# LINEARDriver_MCU.net
KiCad netlist of a schematic drawn in Altium Designer
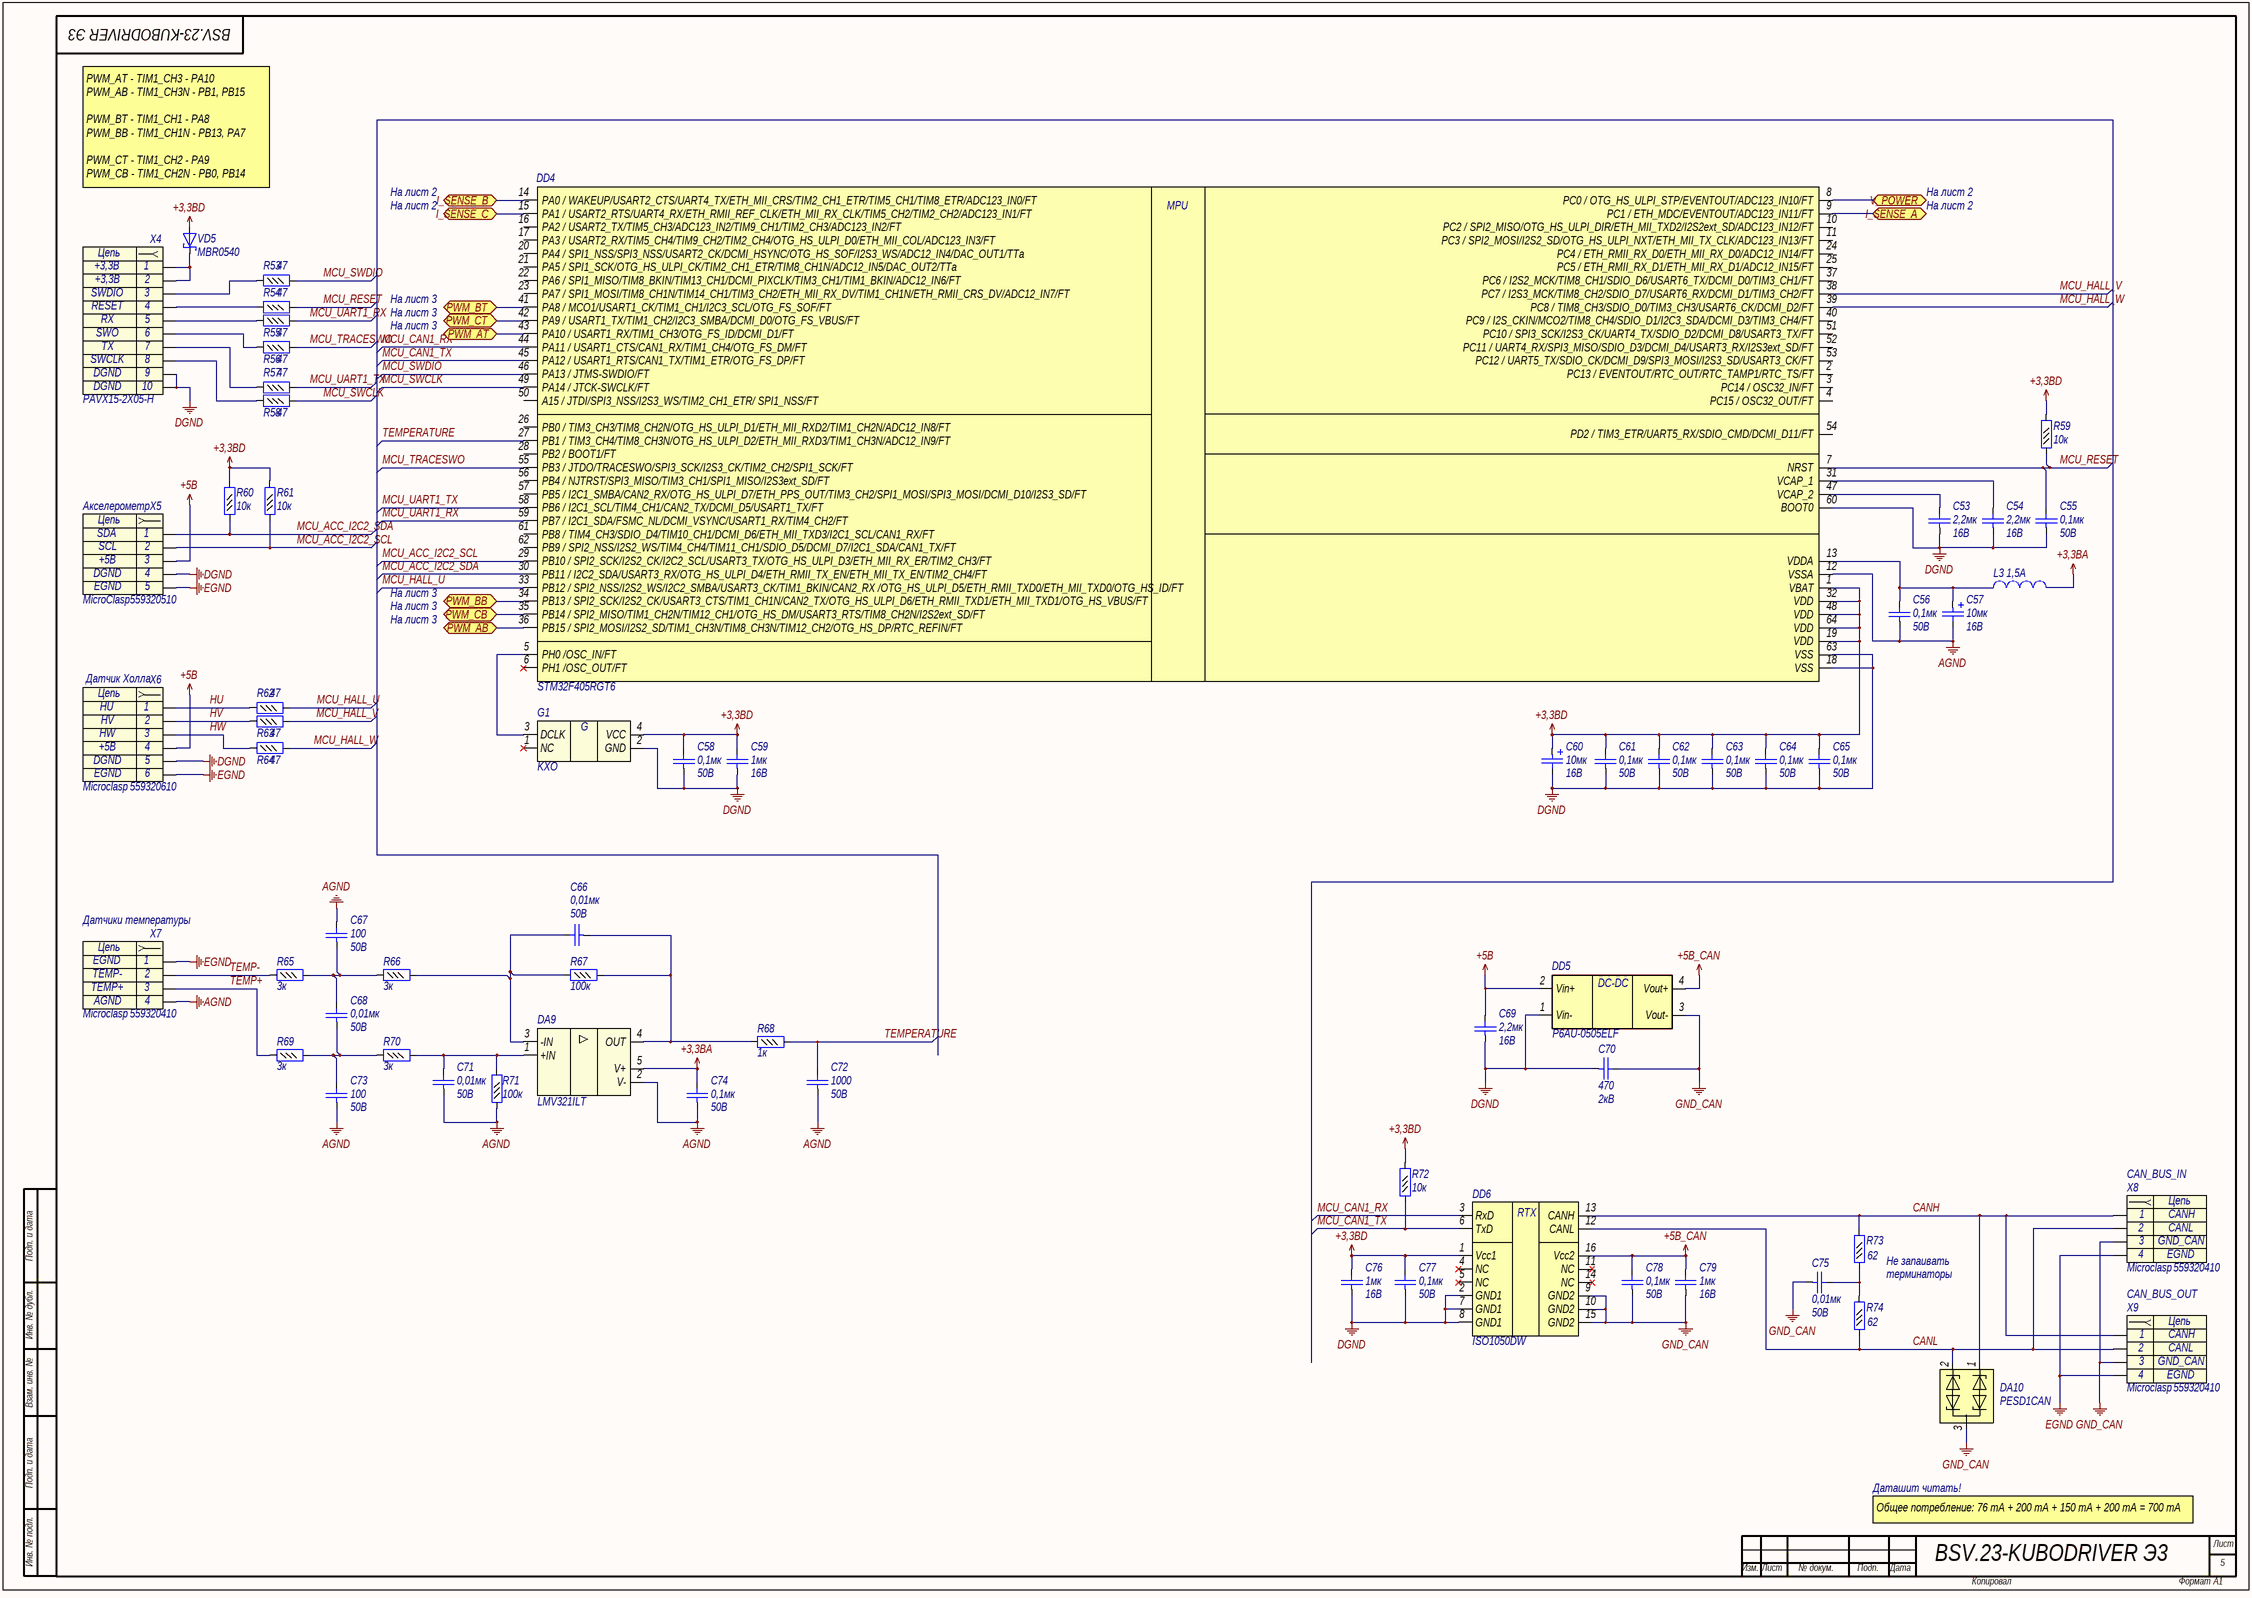
[diagram p0: LINEARDriver_MCU.SchDoc]

(export (version "E")
  (design (tool "Eeschema 10.0.6"))
  (components
    (comp (ref "C53")
      (value "2,2мк")
      (footprint "C0603")
      (description "Конденсатор")
      (fields (field (name "VOLTAGE") "16B") (field (name "PART NUMBER") "GRM188Z71C225ME43J"))
      (libsource (lib "MOP44") (part "Capacitor"))
    )
    (comp (ref "C54")
      (value "2,2мк")
      (footprint "C0603")
      (description "Конденсатор")
      (fields (field (name "VOLTAGE") "16B") (field (name "PART NUMBER") "GRM188Z71C225ME43J"))
      (libsource (lib "MOP44") (part "Capacitor"))
    )
    (comp (ref "C55")
      (value "0,1мк")
      (footprint "C0402")
      (description "Конденсатор")
      (fields
        (field (name "VOLTAGE") "50В")
        (field (name "PART NUMBER") "GRM155R71H104KE14D ")
        (field (name "Comment") "Capacitor")
      )
      (libsource (lib "MOP44") (part "Capacitor"))
    )
    (comp (ref "C56")
      (value "0,1мк")
      (footprint "C0402")
      (description "Конденсатор")
      (fields
        (field (name "VOLTAGE") "50В")
        (field (name "PART NUMBER") "GRM155R71H104KE14D ")
        (field (name "Comment") "Capacitor")
      )
      (libsource (lib "MOP44") (part "Capacitor"))
    )
    (comp (ref "C57")
      (value "10мк")
      (footprint "TANTAL CASE A")
      (description "Конденсатор полярный")
      (fields
        (field (name "VOLTAGE") "16В")
        (field (name "PART NUMBER") "293D106X9016A2TE3")
        (field (name "Comment") "Capacitor_pol")
      )
      (libsource (lib "MOP44") (part "Capacitor_pol"))
    )
    (comp (ref "C58")
      (value "0,1мк")
      (footprint "C0402")
      (description "Конденсатор")
      (fields
        (field (name "VOLTAGE") "50В")
        (field (name "PART NUMBER") "GRM155R71H104KE14D ")
        (field (name "Comment") "Capacitor")
      )
      (libsource (lib "MOP44") (part "Capacitor"))
    )
    (comp (ref "C59")
      (value "1мк")
      (footprint "C0603")
      (description "Конденсатор")
      (fields
        (field (name "VOLTAGE") "16B")
        (field (name "PART NUMBER") "GRM188R71C105KA12D**")
        (field (name "Comment") "Capacitor")
      )
      (libsource (lib "MOP44") (part "Capacitor"))
    )
    (comp (ref "C60")
      (value "10мк")
      (footprint "TANTAL CASE A")
      (description "Конденсатор полярный")
      (fields
        (field (name "VOLTAGE") "16В")
        (field (name "PART NUMBER") "293D106X9016A2TE3")
        (field (name "Comment") "Capacitor_pol")
      )
      (libsource (lib "MOP44") (part "Capacitor_pol"))
    )
    (comp (ref "C61")
      (value "0,1мк")
      (footprint "C0402")
      (description "Конденсатор")
      (fields
        (field (name "VOLTAGE") "50В")
        (field (name "PART NUMBER") "GRM155R71H104KE14D ")
        (field (name "Comment") "Capacitor")
      )
      (libsource (lib "MOP44") (part "Capacitor"))
    )
    (comp (ref "C62")
      (value "0,1мк")
      (footprint "C0402")
      (description "Конденсатор")
      (fields
        (field (name "VOLTAGE") "50В")
        (field (name "PART NUMBER") "GRM155R71H104KE14D ")
        (field (name "Comment") "Capacitor")
      )
      (libsource (lib "MOP44") (part "Capacitor"))
    )
    (comp (ref "C63")
      (value "0,1мк")
      (footprint "C0402")
      (description "Конденсатор")
      (fields
        (field (name "VOLTAGE") "50В")
        (field (name "PART NUMBER") "GRM155R71H104KE14D ")
        (field (name "Comment") "Capacitor")
      )
      (libsource (lib "MOP44") (part "Capacitor"))
    )
    (comp (ref "C64")
      (value "0,1мк")
      (footprint "C0402")
      (description "Конденсатор")
      (fields
        (field (name "VOLTAGE") "50В")
        (field (name "PART NUMBER") "GRM155R71H104KE14D ")
        (field (name "Comment") "Capacitor")
      )
      (libsource (lib "MOP44") (part "Capacitor"))
    )
    (comp (ref "C65")
      (value "0,1мк")
      (footprint "C0402")
      (description "Конденсатор")
      (fields
        (field (name "VOLTAGE") "50В")
        (field (name "PART NUMBER") "GRM155R71H104KE14D ")
        (field (name "Comment") "Capacitor")
      )
      (libsource (lib "MOP44") (part "Capacitor"))
    )
    (comp (ref "C66")
      (value "0,01мк")
      (footprint "C0402")
      (description "Конденсатор")
      (fields
        (field (name "VOLTAGE") "50B")
        (field (name "PART NUMBER") "GRM155R71H103K")
        (field (name "Comment") "Capacitor")
      )
      (libsource (lib "MOP44") (part "Capacitor"))
    )
    (comp (ref "C67")
      (value "100")
      (footprint "C0402")
      (description "Конденсатор")
      (fields
        (field (name "VOLTAGE") "50B")
        (field (name "PART NUMBER") "GRM1535C1H101J")
        (field (name "Comment") "Capacitor")
      )
      (libsource (lib "MOP44") (part "Capacitor"))
    )
    (comp (ref "C68")
      (value "0,01мк")
      (footprint "C0402")
      (description "Конденсатор")
      (fields
        (field (name "VOLTAGE") "50B")
        (field (name "PART NUMBER") "GRM155R71H103K")
        (field (name "Comment") "Capacitor")
      )
      (libsource (lib "MOP44") (part "Capacitor"))
    )
    (comp (ref "C69")
      (value "2,2мк")
      (footprint "C0603")
      (description "Конденсатор")
      (fields (field (name "VOLTAGE") "16B") (field (name "PART NUMBER") "GRM188Z71C225ME43J"))
      (libsource (lib "MOP44") (part "Capacitor"))
    )
    (comp (ref "C70")
      (value "470")
      (footprint "C1206")
      (description "Конденсатор")
      (fields
        (field (name "VOLTAGE") "2кВ")
        (field (name "PART NUMBER") "CC1206KKX7RDBB471 ")
        (field (name "Comment") "Capacitor")
      )
      (libsource (lib "MOP44") (part "Capacitor"))
    )
    (comp (ref "C71")
      (value "0,01мк")
      (footprint "C0402")
      (description "Конденсатор")
      (fields
        (field (name "VOLTAGE") "50B")
        (field (name "PART NUMBER") "GRM155R71H103K")
        (field (name "Comment") "Capacitor")
      )
      (libsource (lib "MOP44") (part "Capacitor"))
    )
    (comp (ref "C72")
      (value "1000")
      (footprint "C0402")
      (description "Конденсатор")
      (fields
        (field (name "VOLTAGE") "50B")
        (field (name "PART NUMBER") "GRM1555C1H102J")
        (field (name "Comment") "Capacitor")
      )
      (libsource (lib "MOP44") (part "Capacitor"))
    )
    (comp (ref "C73")
      (value "100")
      (footprint "C0402")
      (description "Конденсатор")
      (fields
        (field (name "VOLTAGE") "50B")
        (field (name "PART NUMBER") "GRM1535C1H101J")
        (field (name "Comment") "Capacitor")
      )
      (libsource (lib "MOP44") (part "Capacitor"))
    )
    (comp (ref "C74")
      (value "0,1мк")
      (footprint "C0402")
      (description "Конденсатор")
      (fields
        (field (name "VOLTAGE") "50В")
        (field (name "PART NUMBER") "GRM155R71H104KE14D ")
        (field (name "Comment") "Capacitor")
      )
      (libsource (lib "MOP44") (part "Capacitor"))
    )
    (comp (ref "C75")
      (value "0,01мк")
      (footprint "C0402")
      (description "Конденсатор")
      (fields
        (field (name "VOLTAGE") "50B")
        (field (name "PART NUMBER") "GRM155R71H103K")
        (field (name "Comment") "Capacitor")
      )
      (libsource (lib "MOP44") (part "Capacitor"))
    )
    (comp (ref "C76")
      (value "1мк")
      (footprint "C0603")
      (description "Конденсатор")
      (fields
        (field (name "VOLTAGE") "16B")
        (field (name "PART NUMBER") "GRM188R71C105KA12D**")
        (field (name "Comment") "Capacitor")
      )
      (libsource (lib "MOP44") (part "Capacitor"))
    )
    (comp (ref "C77")
      (value "0,1мк")
      (footprint "C0402")
      (description "Конденсатор")
      (fields
        (field (name "VOLTAGE") "50В")
        (field (name "PART NUMBER") "GRM155R71H104KE14D ")
        (field (name "Comment") "Capacitor")
      )
      (libsource (lib "MOP44") (part "Capacitor"))
    )
    (comp (ref "C78")
      (value "0,1мк")
      (footprint "C0402")
      (description "Конденсатор")
      (fields
        (field (name "VOLTAGE") "50В")
        (field (name "PART NUMBER") "GRM155R71H104KE14D ")
        (field (name "Comment") "Capacitor")
      )
      (libsource (lib "MOP44") (part "Capacitor"))
    )
    (comp (ref "C79")
      (value "1мк")
      (footprint "C0603")
      (description "Конденсатор")
      (fields
        (field (name "VOLTAGE") "16B")
        (field (name "PART NUMBER") "GRM188R71C105KA12D**")
        (field (name "Comment") "Capacitor")
      )
      (libsource (lib "MOP44") (part "Capacitor"))
    )
    (comp (ref "DA9")
      (value "LMV321ILT")
      (footprint "SOT23-5")
      (description "HIGH-DRIVE OPERATIONAL AMPLIFIERS WITH SHUTDOWN")
      (libsource (lib "MOP44") (part "LMV321ILT"))
    )
    (comp (ref "DA10")
      (value "PESD")
      (footprint "SOT23-3")
      (description "TVS")
      (fields (field (name "PART NUMBER") "PESD1CAN"))
      (libsource (lib "MOP44") (part "PESD"))
    )
    (comp (ref "DD4")
      (value "STM32F405RGT6")
      (footprint "LQFP64")
      (libsource (lib "MOP44") (part "STM32F405RGT6"))
    )
    (comp (ref "DD5")
      (value "P6AU-xxxxELF")
      (footprint "SIP4")
      (description "DC/DC преобразователь")
      (fields (field (name "PART NUMBER") "P6AU-0505ELF") (field (name "MANUFACTURER") "PEAK Electronics"))
      (libsource (lib "MOP44") (part "P6AU-xxxxELF"))
    )
    (comp (ref "DD6")
      (value "~")
      (footprint "SO16")
      (description "Isolated CAN Transceiver")
      (fields (field (name "PART NUMBER") "ISO1050DW"))
      (libsource (lib "MOP44") (part "ISO1050DW"))
    )
    (comp (ref "G1")
      (value "KXO")
      (footprint "QSMD7x5.2x1.8")
      (description "Кварц. генер. 32.768 МГц (HCMOS/TTL)")
      (fields (field (name "PART NUMBER") "KXO-V97"))
      (libsource (lib "MOP44") (part "KXO"))
    )
    (comp (ref "L3")
      (value "Inductor")
      (footprint "L0603")
      (description "EMI Suppression Filter")
      (fields (field (name "RATED CURRENT") "1,5A") (field (name "PART NUMBER") "BLM18PG181SN1D"))
      (libsource (lib "MOP44") (part "Inductor"))
    )
    (comp (ref "R53")
      (value "47")
      (footprint "R0402")
      (description "Резистор")
      (fields (field (name "PART NUMBER") "RC0402FR-0747RL") (field (name "POWER") "0,062Вт"))
      (libsource (lib "MOP44") (part "Resistor_0,062Вт"))
    )
    (comp (ref "R54")
      (value "47")
      (footprint "R0402")
      (description "Резистор")
      (fields (field (name "PART NUMBER") "RC0402FR-0747RL") (field (name "POWER") "0,062Вт"))
      (libsource (lib "MOP44") (part "Resistor_0,062Вт"))
    )
    (comp (ref "R55")
      (value "47")
      (footprint "R0402")
      (description "Резистор")
      (fields (field (name "PART NUMBER") "RC0402FR-0747RL") (field (name "POWER") "0,062Вт"))
      (libsource (lib "MOP44") (part "Resistor_0,062Вт"))
    )
    (comp (ref "R56")
      (value "47")
      (footprint "R0402")
      (description "Резистор")
      (fields (field (name "PART NUMBER") "RC0402FR-0747RL") (field (name "POWER") "0,062Вт"))
      (libsource (lib "MOP44") (part "Resistor_0,062Вт"))
    )
    (comp (ref "R57")
      (value "47")
      (footprint "R0402")
      (description "Резистор")
      (fields (field (name "PART NUMBER") "RC0402FR-0747RL") (field (name "POWER") "0,062Вт"))
      (libsource (lib "MOP44") (part "Resistor_0,062Вт"))
    )
    (comp (ref "R58")
      (value "47")
      (footprint "R0402")
      (description "Резистор")
      (fields (field (name "PART NUMBER") "RC0402FR-0747RL") (field (name "POWER") "0,062Вт"))
      (libsource (lib "MOP44") (part "Resistor_0,062Вт"))
    )
    (comp (ref "R59")
      (value "10к")
      (footprint "R0402")
      (description "Резистор")
      (fields (field (name "PART NUMBER") "RC0402FR-0710KL") (field (name "POWER") "0,062Вт"))
      (libsource (lib "") (part "Resistor_0,062Вт_1"))
    )
    (comp (ref "R60")
      (value "10к")
      (footprint "R0402")
      (description "Резистор")
      (fields (field (name "PART NUMBER") "RC0402FR-0710KL") (field (name "POWER") "0,062Вт"))
      (libsource (lib "") (part "Resistor_0,062Вт_1"))
    )
    (comp (ref "R61")
      (value "10к")
      (footprint "R0402")
      (description "Резистор")
      (fields (field (name "PART NUMBER") "RC0402FR-0710KL") (field (name "POWER") "0,062Вт"))
      (libsource (lib "") (part "Resistor_0,062Вт_1"))
    )
    (comp (ref "R62")
      (value "47")
      (footprint "R0402")
      (description "Резистор")
      (fields (field (name "PART NUMBER") "RC0402FR-0747RL") (field (name "POWER") "0,062Вт"))
      (libsource (lib "MOP44") (part "Resistor_0,062Вт"))
    )
    (comp (ref "R63")
      (value "47")
      (footprint "R0402")
      (description "Резистор")
      (fields (field (name "PART NUMBER") "RC0402FR-0747RL") (field (name "POWER") "0,062Вт"))
      (libsource (lib "MOP44") (part "Resistor_0,062Вт"))
    )
    (comp (ref "R64")
      (value "47")
      (footprint "R0402")
      (description "Резистор")
      (fields (field (name "PART NUMBER") "RC0402FR-0747RL") (field (name "POWER") "0,062Вт"))
      (libsource (lib "MOP44") (part "Resistor_0,062Вт"))
    )
    (comp (ref "R65")
      (value "3к")
      (footprint "R0402")
      (description "Резистор")
      (fields (field (name "PART NUMBER") "RC0402FR-073KL") (field (name "POWER") "0,062Вт"))
      (libsource (lib "MOP44") (part "Resistor_0,062Вт"))
    )
    (comp (ref "R66")
      (value "3к")
      (footprint "R0402")
      (description "Резистор")
      (fields (field (name "PART NUMBER") "RC0402FR-073KL") (field (name "POWER") "0,062Вт"))
      (libsource (lib "MOP44") (part "Resistor_0,062Вт"))
    )
    (comp (ref "R67")
      (value "100к")
      (footprint "R0402")
      (description "Резистор")
      (fields (field (name "PART NUMBER") "RC0402FR-07100KL") (field (name "POWER") "0,062Вт"))
      (libsource (lib "MOP44") (part "Resistor_0,062Вт"))
    )
    (comp (ref "R68")
      (value "1к")
      (footprint "R0402")
      (description "Резистор")
      (fields (field (name "PART NUMBER") "RC0402FR-071KL") (field (name "POWER") "0,062Вт"))
      (libsource (lib "MOP44") (part "Resistor_0,062Вт"))
    )
    (comp (ref "R69")
      (value "3к")
      (footprint "R0402")
      (description "Резистор")
      (fields (field (name "PART NUMBER") "RC0402FR-073KL") (field (name "POWER") "0,062Вт"))
      (libsource (lib "MOP44") (part "Resistor_0,062Вт"))
    )
    (comp (ref "R70")
      (value "3к")
      (footprint "R0402")
      (description "Резистор")
      (fields (field (name "PART NUMBER") "RC0402FR-073KL") (field (name "POWER") "0,062Вт"))
      (libsource (lib "MOP44") (part "Resistor_0,062Вт"))
    )
    (comp (ref "R71")
      (value "100к")
      (footprint "R0402")
      (description "Резистор")
      (fields (field (name "PART NUMBER") "RC0402FR-07100KL") (field (name "POWER") "0,062Вт"))
      (libsource (lib "") (part "Resistor_0,062Вт_1"))
    )
    (comp (ref "R72")
      (value "10к")
      (footprint "R0402")
      (description "Резистор")
      (fields (field (name "PART NUMBER") "RC0402FR-0710KL") (field (name "POWER") "0,062Вт"))
      (libsource (lib "") (part "Resistor_0,062Вт_1"))
    )
    (comp (ref "R73")
      (value "62")
      (footprint "R0402")
      (description "Резистор")
      (fields (field (name "PART NUMBER") "RC0402FR-0762RL") (field (name "POWER") "0,062Вт"))
      (libsource (lib "") (part "Resistor_0,062Вт_1"))
    )
    (comp (ref "R74")
      (value "62")
      (footprint "R0402")
      (description "Резистор")
      (fields (field (name "PART NUMBER") "RC0402FR-0762RL") (field (name "POWER") "0,062Вт"))
      (libsource (lib "") (part "Resistor_0,062Вт_1"))
    )
    (comp (ref "VD5")
      (value "DiodeSchottky")
      (footprint "SOD-123")
      (description "Диод Шоттки")
      (fields (field (name "PART NUMBER") "MBR0540"))
      (libsource (lib "MOP44") (part "DiodeSchottky"))
    )
    (comp (ref "X4")
      (value "Header_10_sct")
      (footprint "PAVX15-2X05-H")
      (description "Разъем - 10 конт. розетка")
      (fields (field (name "PART NUMBER") "PAVX15-2X05-H"))
      (libsource (lib "MOP44") (part "Header_10_sct"))
    )
    (comp (ref "X5")
      (value "Акселерометр")
      (footprint "MOLEX_559320510")
      (description "Разъем - 5 конт. розетка")
      (fields (field (name "PART NAME") "MicroClasp") (field (name "PART NUMBER") "559320510"))
      (libsource (lib "MOP44") (part "Header_5_sct"))
    )
    (comp (ref "X6")
      (value "Датчик Холла")
      (footprint "MOLEX_559320610")
      (description "Разъем - 6 конт. розетка")
      (fields (field (name "PART NUMBER") "559320610"))
      (libsource (lib "MOP44") (part "Header_6_sct"))
    )
    (comp (ref "X7")
      (value "Датчики температуры")
      (footprint "MOLEX_559320410")
      (description "Разъем - 4 конт. розетка")
      (fields (field (name "PART NUMBER") "559320410"))
      (libsource (lib "MOP44") (part "Header_4_sct"))
    )
    (comp (ref "X8")
      (value "CAN_BUS_IN")
      (footprint "MOLEX_559320410")
      (description "Разъем - 4 конт. розетка")
      (fields (field (name "PART NUMBER") "559320410"))
      (libsource (lib "") (part "Header_4_sct_1"))
    )
    (comp (ref "X9")
      (value "CAN_BUS_OUT")
      (footprint "MOLEX_559320410")
      (description "Разъем - 4 конт. розетка")
      (fields (field (name "PART NUMBER") "559320410"))
      (libsource (lib "") (part "Header_4_sct_1"))
    )
  )
  (nets
    (net (code "1") (name "+3,3BA") (class "Default")
      (node (ref "C74") (pin "2") (pinfunction "2_2") (pintype "passive"))
      (node (ref "DA9") (pin "5") (pinfunction "V+_5") (pintype "passive"))
      (node (ref "L3") (pin "2") (pinfunction "2_2") (pintype "passive"))
    )
    (net (code "2") (name "+3,3BD") (class "Default")
      (node (ref "C58") (pin "2") (pinfunction "2_2") (pintype "passive"))
      (node (ref "C59") (pin "2") (pinfunction "2_2") (pintype "passive"))
      (node (ref "C60") (pin "1") (pinfunction "1_1") (pintype "passive"))
      (node (ref "C61") (pin "2") (pinfunction "2_2") (pintype "passive"))
      (node (ref "C62") (pin "2") (pinfunction "2_2") (pintype "passive"))
      (node (ref "C63") (pin "2") (pinfunction "2_2") (pintype "passive"))
      (node (ref "C64") (pin "2") (pinfunction "2_2") (pintype "passive"))
      (node (ref "C65") (pin "2") (pinfunction "2_2") (pintype "passive"))
      (node (ref "C76") (pin "2") (pinfunction "2_2") (pintype "passive"))
      (node (ref "C77") (pin "2") (pinfunction "2_2") (pintype "passive"))
      (node (ref "DD4") (pin "1") (pinfunction "VBAT_1") (pintype "passive"))
      (node (ref "DD4") (pin "19") (pinfunction "VDD_19") (pintype "passive"))
      (node (ref "DD4") (pin "32") (pinfunction "VDD_32") (pintype "passive"))
      (node (ref "DD4") (pin "48") (pinfunction "VDD_48") (pintype "passive"))
      (node (ref "DD4") (pin "64") (pinfunction "VDD_64") (pintype "passive"))
      (node (ref "DD6") (pin "1") (pinfunction "Vcc1_1") (pintype "passive"))
      (node (ref "G1") (pin "4") (pinfunction "VCC_4") (pintype "power_in"))
      (node (ref "R59") (pin "2") (pinfunction "2_2") (pintype "passive"))
      (node (ref "R60") (pin "2") (pinfunction "2_2") (pintype "passive"))
      (node (ref "R61") (pin "2") (pinfunction "2_2") (pintype "passive"))
      (node (ref "R72") (pin "2") (pinfunction "2_2") (pintype "passive"))
      (node (ref "VD5") (pin "2") (pinfunction "A_2") (pintype "passive"))
    )
    (net (code "3") (name "+5B") (class "Default")
      (node (ref "C69") (pin "2") (pinfunction "2_2") (pintype "passive"))
      (node (ref "DD5") (pin "2") (pinfunction "Vin+_2") (pintype "passive"))
      (node (ref "X5") (pin "3") (pinfunction "3_3") (pintype "passive"))
      (node (ref "X6") (pin "4") (pinfunction "4_4") (pintype "passive"))
    )
    (net (code "4") (name "+5B_CAN") (class "Default")
      (node (ref "C78") (pin "2") (pinfunction "2_2") (pintype "passive"))
      (node (ref "C79") (pin "2") (pinfunction "2_2") (pintype "passive"))
      (node (ref "DD5") (pin "4") (pinfunction "Vout+_4") (pintype "passive"))
      (node (ref "DD6") (pin "16") (pinfunction "Vcc2_16") (pintype "passive"))
    )
    (net (code "5") (name "/CANH") (class "Default")
      (node (ref "DA10") (pin "1") (pintype "passive"))
      (node (ref "DD6") (pin "13") (pinfunction "CANH_13") (pintype "passive"))
      (node (ref "R73") (pin "2") (pinfunction "2_2") (pintype "passive"))
      (node (ref "X8") (pin "1") (pinfunction "1_1") (pintype "passive"))
      (node (ref "X9") (pin "1") (pinfunction "1_1") (pintype "passive"))
    )
    (net (code "6") (name "/CANL") (class "Default")
      (node (ref "DA10") (pin "2") (pinfunction "1_2") (pintype "passive"))
      (node (ref "DD6") (pin "12") (pinfunction "CANL_12") (pintype "passive"))
      (node (ref "R74") (pin "1") (pinfunction "1_1") (pintype "passive"))
      (node (ref "X8") (pin "2") (pinfunction "2_2") (pintype "passive"))
      (node (ref "X9") (pin "2") (pinfunction "2_2") (pintype "passive"))
    )
    (net (code "7") (name "/HU") (class "Default")
      (node (ref "R62") (pin "1") (pinfunction "1_1") (pintype "passive"))
      (node (ref "X6") (pin "1") (pinfunction "1_1") (pintype "passive"))
    )
    (net (code "8") (name "/HV") (class "Default")
      (node (ref "R63") (pin "1") (pinfunction "1_1") (pintype "passive"))
      (node (ref "X6") (pin "2") (pinfunction "2_2") (pintype "passive"))
    )
    (net (code "9") (name "/HW") (class "Default")
      (node (ref "R64") (pin "1") (pinfunction "1_1") (pintype "passive"))
      (node (ref "X6") (pin "3") (pinfunction "3_3") (pintype "passive"))
    )
    (net (code "10") (name "/I_SENSE_A") (class "Default")
      (node (ref "DD4") (pin "9") (pinfunction "PC1_/_ETH_MDC/EVENTOUT/ADC123_IN11/FT_9") (pintype "passive"))
    )
    (net (code "11") (name "/I_SENSE_B") (class "Default")
      (node (ref "DD4") (pin "14") (pinfunction "PA0_/_WAKEUP/USART2_CTS/UART4_TX/ETH_MII_CRS/TIM2_CH1_ETR/TIM5_CH1/TIM8_ETR/ADC123_IN0/FT_14") (pintype "passive"))
    )
    (net (code "12") (name "/I_SENSE_C") (class "Default")
      (node (ref "DD4") (pin "15") (pinfunction "PA1_/_USART2_RTS/UART4_RX/ETH_RMII_REF_CLK/ETH_MII_RX_CLK/TIM5_CH2/TIM2_CH2/ADC123_IN1/FT_15") (pintype "passive"))
    )
    (net (code "13") (name "/MCU_ACC_I2C2_SCL") (class "Default")
      (node (ref "DD4") (pin "29") (pinfunction "PB10_/_SPI2_SCK/I2S2_CK/I2C2_SCL/USART3_TX/OTG_HS_ULPI_D3/ETH_MII_RX_ER/TIM2_CH3/FT_29") (pintype "passive"))
      (node (ref "R61") (pin "1") (pinfunction "1_1") (pintype "passive"))
      (node (ref "X5") (pin "2") (pinfunction "2_2") (pintype "passive"))
    )
    (net (code "14") (name "/MCU_ACC_I2C2_SDA") (class "Default")
      (node (ref "DD4") (pin "30") (pinfunction "PB11_/_I2C2_SDA/USART3_RX/OTG_HS_ULPI_D4/ETH_RMII_TX_EN/ETH_MII_TX_EN/TIM2_CH4/FT_30") (pintype "passive"))
      (node (ref "R60") (pin "1") (pinfunction "1_1") (pintype "passive"))
      (node (ref "X5") (pin "1") (pinfunction "1_1") (pintype "passive"))
    )
    (net (code "15") (name "/MCU_CAN1_RX") (class "Default")
      (node (ref "DD4") (pin "44") (pinfunction "PA11_/_USART1_CTS/CAN1_RX/TIM1_CH4/OTG_FS_DM/FT_44") (pintype "passive"))
      (node (ref "DD6") (pin "3") (pinfunction "RxD_3") (pintype "passive"))
    )
    (net (code "16") (name "/MCU_CAN1_TX") (class "Default")
      (node (ref "DD4") (pin "45") (pinfunction "PA12_/_USART1_RTS/CAN1_TX/TIM1_ETR/OTG_FS_DP/FT_45") (pintype "passive"))
      (node (ref "DD6") (pin "6") (pinfunction "TxD_6") (pintype "passive"))
      (node (ref "R72") (pin "1") (pinfunction "1_1") (pintype "passive"))
    )
    (net (code "17") (name "/MCU_HALL_U") (class "Default")
      (node (ref "DD4") (pin "33") (pinfunction "PB12_/_SPI2_NSS/I2S2_WS/I2C2_SMBA/USART3_CK/TIM1_BKIN/CAN2_RX_/OTG_HS_ULPI_D5/ETH_RMII_TXD0/ETH_MII_TXD0/OTG_HS_ID/FT_33") (pintype "passive"))
      (node (ref "R62") (pin "2") (pinfunction "2_2") (pintype "passive"))
    )
    (net (code "18") (name "/MCU_HALL_V") (class "Default")
      (node (ref "DD4") (pin "38") (pinfunction "PC7_/_I2S3_MCK/TIM8_CH2/SDIO_D7/USART6_RX/DCMI_D1/TIM3_CH2/FT_38") (pintype "passive"))
      (node (ref "R63") (pin "2") (pinfunction "2_2") (pintype "passive"))
    )
    (net (code "19") (name "/MCU_HALL_W") (class "Default")
      (node (ref "DD4") (pin "39") (pinfunction "PC8_/_TIM8_CH3/SDIO_D0/TIM3_CH3/USART6_CK/DCMI_D2/FT_39") (pintype "passive"))
      (node (ref "R64") (pin "2") (pinfunction "2_2") (pintype "passive"))
    )
    (net (code "20") (name "/MCU_RESET") (class "Default")
      (node (ref "C55") (pin "2") (pinfunction "2_2") (pintype "passive"))
      (node (ref "DD4") (pin "7") (pinfunction "NRST_7") (pintype "passive"))
      (node (ref "R54") (pin "2") (pinfunction "2_2") (pintype "passive"))
      (node (ref "R59") (pin "1") (pinfunction "1_1") (pintype "passive"))
    )
    (net (code "21") (name "/MCU_SWCLK") (class "Default")
      (node (ref "DD4") (pin "49") (pinfunction "PA14_/_JTCK-SWCLK/FT_49") (pintype "passive"))
      (node (ref "R58") (pin "2") (pinfunction "2_2") (pintype "passive"))
    )
    (net (code "22") (name "/MCU_SWDIO") (class "Default")
      (node (ref "DD4") (pin "46") (pinfunction "PA13_/_JTMS-SWDIO/FT_46") (pintype "passive"))
      (node (ref "R53") (pin "2") (pinfunction "2_2") (pintype "passive"))
    )
    (net (code "23") (name "/MCU_TRACESWO") (class "Default")
      (node (ref "DD4") (pin "55") (pinfunction "PB3_/_JTDO/TRACESWO/SPI3_SCK/I2S3_CK/TIM2_CH2/SPI1_SCK/FT_55") (pintype "passive"))
      (node (ref "R56") (pin "2") (pinfunction "2_2") (pintype "passive"))
    )
    (net (code "24") (name "/MCU_UART1_RX") (class "Default")
      (node (ref "DD4") (pin "59") (pinfunction "PB7_/_I2C1_SDA/FSMC_NL/DCMI_VSYNC/USART1_RX/TIM4_CH2/FT_59") (pintype "passive"))
      (node (ref "R55") (pin "2") (pinfunction "2_2") (pintype "passive"))
    )
    (net (code "25") (name "/MCU_UART1_TX") (class "Default")
      (node (ref "DD4") (pin "58") (pinfunction "PB6_/_I2C1_SCL/TIM4_CH1/CAN2_TX/DCMI_D5/USART1_TX/FT_58") (pintype "passive"))
      (node (ref "R57") (pin "2") (pinfunction "2_2") (pintype "passive"))
    )
    (net (code "26") (name "/PWM_AB") (class "Default")
      (node (ref "DD4") (pin "36") (pinfunction "PB15_/_SPI2_MOSI/I2S2_SD/TIM1_CH3N/TIM8_CH3N/TIM12_CH2/OTG_HS_DP/RTC_REFIN/FT_36") (pintype "passive"))
    )
    (net (code "27") (name "/PWM_AT") (class "Default")
      (node (ref "DD4") (pin "43") (pinfunction "PA10_/_USART1_RX/TIM1_CH3/OTG_FS_ID/DCMI_D1/FT_43") (pintype "passive"))
    )
    (net (code "28") (name "/PWM_BB") (class "Default")
      (node (ref "DD4") (pin "34") (pinfunction "PB13_/_SPI2_SCK/I2S2_CK/USART3_CTS/TIM1_CH1N/CAN2_TX/OTG_HS_ULPI_D6/ETH_RMII_TXD1/ETH_MII_TXD1/OTG_HS_VBUS/FT_34") (pintype "passive"))
    )
    (net (code "29") (name "/PWM_BT") (class "Default")
      (node (ref "DD4") (pin "41") (pinfunction "PA8_/_MCO1/USART1_CK/TIM1_CH1/I2C3_SCL/OTG_FS_SOF/FT_41") (pintype "passive"))
    )
    (net (code "30") (name "/PWM_CB") (class "Default")
      (node (ref "DD4") (pin "35") (pinfunction "PB14_/_SPI2_MISO/TIM1_CH2N/TIM12_CH1/OTG_HS_DM/USART3_RTS/TIM8_CH2N/I2S2ext_SD/FT_35") (pintype "passive"))
    )
    (net (code "31") (name "/PWM_CT") (class "Default")
      (node (ref "DD4") (pin "42") (pinfunction "PA9_/_USART1_TX/TIM1_CH2/I2C3_SMBA/DCMI_D0/OTG_FS_VBUS/FT_42") (pintype "passive"))
    )
    (net (code "32") (name "/TEMP+") (class "Default")
      (node (ref "R69") (pin "1") (pinfunction "1_1") (pintype "passive"))
      (node (ref "X7") (pin "3") (pinfunction "3_3") (pintype "passive"))
    )
    (net (code "33") (name "/TEMP-") (class "Default")
      (node (ref "R65") (pin "1") (pinfunction "1_1") (pintype "passive"))
      (node (ref "X7") (pin "2") (pinfunction "2_2") (pintype "passive"))
    )
    (net (code "34") (name "/TEMPERATURE") (class "Default")
      (node (ref "C72") (pin "2") (pinfunction "2_2") (pintype "passive"))
      (node (ref "DD4") (pin "27") (pinfunction "PB1_/_TIM3_CH4/TIM8_CH3N/OTG_HS_ULPI_D2/ETH_MII_RXD3/TIM1_CH3N/ADC12_IN9/FT_27") (pintype "passive"))
      (node (ref "R68") (pin "2") (pinfunction "2_2") (pintype "passive"))
    )
    (net (code "35") (name "/V_POWER") (class "Default")
      (node (ref "DD4") (pin "8") (pinfunction "PC0_/_OTG_HS_ULPI_STP/EVENTOUT/ADC123_IN10/FT_8") (pintype "passive"))
    )
    (net (code "36") (name "AGND") (class "Default")
      (node (ref "C56") (pin "1") (pinfunction "1_1") (pintype "passive"))
      (node (ref "C57") (pin "2") (pinfunction "2_2") (pintype "passive"))
      (node (ref "C67") (pin "2") (pinfunction "2_2") (pintype "passive"))
      (node (ref "C71") (pin "1") (pinfunction "1_1") (pintype "passive"))
      (node (ref "C72") (pin "1") (pinfunction "1_1") (pintype "passive"))
      (node (ref "C73") (pin "1") (pinfunction "1_1") (pintype "passive"))
      (node (ref "C74") (pin "1") (pinfunction "1_1") (pintype "passive"))
      (node (ref "DA9") (pin "2") (pinfunction "V-_2") (pintype "passive"))
      (node (ref "DD4") (pin "12") (pinfunction "VSSA_12") (pintype "passive"))
      (node (ref "R71") (pin "1") (pinfunction "1_1") (pintype "passive"))
      (node (ref "X7") (pin "4") (pinfunction "4_4") (pintype "passive"))
    )
    (net (code "37") (name "DGND") (class "Default")
      (node (ref "C53") (pin "1") (pinfunction "1_1") (pintype "passive"))
      (node (ref "C54") (pin "1") (pinfunction "1_1") (pintype "passive"))
      (node (ref "C55") (pin "1") (pinfunction "1_1") (pintype "passive"))
      (node (ref "C58") (pin "1") (pinfunction "1_1") (pintype "passive"))
      (node (ref "C59") (pin "1") (pinfunction "1_1") (pintype "passive"))
      (node (ref "C60") (pin "2") (pinfunction "2_2") (pintype "passive"))
      (node (ref "C61") (pin "1") (pinfunction "1_1") (pintype "passive"))
      (node (ref "C62") (pin "1") (pinfunction "1_1") (pintype "passive"))
      (node (ref "C63") (pin "1") (pinfunction "1_1") (pintype "passive"))
      (node (ref "C64") (pin "1") (pinfunction "1_1") (pintype "passive"))
      (node (ref "C65") (pin "1") (pinfunction "1_1") (pintype "passive"))
      (node (ref "C69") (pin "1") (pinfunction "1_1") (pintype "passive"))
      (node (ref "C70") (pin "1") (pinfunction "1_1") (pintype "passive"))
      (node (ref "C76") (pin "1") (pinfunction "1_1") (pintype "passive"))
      (node (ref "C77") (pin "1") (pinfunction "1_1") (pintype "passive"))
      (node (ref "DD4") (pin "18") (pinfunction "VSS_18") (pintype "passive"))
      (node (ref "DD4") (pin "60") (pinfunction "BOOT0_60") (pintype "passive"))
      (node (ref "DD4") (pin "63") (pinfunction "VSS_63") (pintype "passive"))
      (node (ref "DD5") (pin "1") (pinfunction "Vin-_1") (pintype "passive"))
      (node (ref "DD6") (pin "2") (pinfunction "GND1_2") (pintype "passive"))
      (node (ref "DD6") (pin "7") (pinfunction "GND1_7") (pintype "passive"))
      (node (ref "DD6") (pin "8") (pinfunction "GND1_8") (pintype "passive"))
      (node (ref "G1") (pin "2") (pinfunction "GND_2") (pintype "power_in"))
      (node (ref "X4") (pin "10") (pinfunction "10_10") (pintype "passive"))
      (node (ref "X4") (pin "9") (pinfunction "9_9") (pintype "passive"))
      (node (ref "X5") (pin "4") (pinfunction "4_4") (pintype "passive"))
      (node (ref "X6") (pin "5") (pinfunction "5_5") (pintype "passive"))
    )
    (net (code "38") (name "EGND") (class "Default")
      (node (ref "X5") (pin "5") (pinfunction "5_5") (pintype "passive"))
      (node (ref "X6") (pin "6") (pinfunction "6_6") (pintype "passive"))
      (node (ref "X7") (pin "1") (pinfunction "1_1") (pintype "passive"))
      (node (ref "X8") (pin "4") (pinfunction "4_4") (pintype "passive"))
      (node (ref "X9") (pin "4") (pinfunction "4_4") (pintype "passive"))
    )
    (net (code "39") (name "GND_CAN") (class "Default")
      (node (ref "C70") (pin "2") (pinfunction "2_2") (pintype "passive"))
      (node (ref "C75") (pin "1") (pinfunction "1_1") (pintype "passive"))
      (node (ref "C78") (pin "1") (pinfunction "1_1") (pintype "passive"))
      (node (ref "C79") (pin "1") (pinfunction "1_1") (pintype "passive"))
      (node (ref "DA10") (pin "3") (pintype "passive"))
      (node (ref "DD5") (pin "3") (pinfunction "Vout-_3") (pintype "passive"))
      (node (ref "DD6") (pin "10") (pinfunction "GND2_10") (pintype "passive"))
      (node (ref "DD6") (pin "15") (pinfunction "GND2_15") (pintype "passive"))
      (node (ref "DD6") (pin "9") (pinfunction "GND2_9") (pintype "passive"))
      (node (ref "X8") (pin "3") (pinfunction "3_3") (pintype "passive"))
      (node (ref "X9") (pin "3") (pinfunction "3_3") (pintype "passive"))
    )
    (net (code "40") (name "Net-(C67-Pad1)") (class "Default")
      (node (ref "C67") (pin "1") (pinfunction "1_1") (pintype "passive"))
      (node (ref "C68") (pin "2") (pinfunction "2_2") (pintype "passive"))
      (node (ref "R65") (pin "2") (pinfunction "2_2") (pintype "passive"))
      (node (ref "R66") (pin "1") (pinfunction "1_1") (pintype "passive"))
    )
    (net (code "41") (name "Net-(C68-Pad1)") (class "Default")
      (node (ref "C68") (pin "1") (pinfunction "1_1") (pintype "passive"))
      (node (ref "C73") (pin "2") (pinfunction "2_2") (pintype "passive"))
      (node (ref "R69") (pin "2") (pinfunction "2_2") (pintype "passive"))
      (node (ref "R70") (pin "1") (pinfunction "1_1") (pintype "passive"))
    )
    (net (code "42") (name "Net-(C75-Pad2)") (class "Default")
      (node (ref "C75") (pin "2") (pinfunction "2_2") (pintype "passive"))
      (node (ref "R73") (pin "1") (pinfunction "1_1") (pintype "passive"))
      (node (ref "R74") (pin "2") (pinfunction "2_2") (pintype "passive"))
    )
    (net (code "43") (name "Net-(DA9-+IN)") (class "Default")
      (node (ref "C71") (pin "2") (pinfunction "2_2") (pintype "passive"))
      (node (ref "DA9") (pin "1") (pinfunction "+IN_1") (pintype "passive"))
      (node (ref "R70") (pin "2") (pinfunction "2_2") (pintype "passive"))
      (node (ref "R71") (pin "2") (pinfunction "2_2") (pintype "passive"))
    )
    (net (code "44") (name "Net-(DA9--IN)") (class "Default")
      (node (ref "C66") (pin "2") (pinfunction "2_2") (pintype "passive"))
      (node (ref "DA9") (pin "3") (pinfunction "-IN_3") (pintype "passive"))
      (node (ref "R66") (pin "2") (pinfunction "2_2") (pintype "passive"))
      (node (ref "R67") (pin "1") (pinfunction "1_1") (pintype "passive"))
    )
    (net (code "45") (name "Net-(DA9-OUT)") (class "Default")
      (node (ref "C66") (pin "1") (pinfunction "1_1") (pintype "passive"))
      (node (ref "DA9") (pin "4") (pinfunction "OUT_4") (pintype "passive"))
      (node (ref "R67") (pin "2") (pinfunction "2_2") (pintype "passive"))
      (node (ref "R68") (pin "1") (pinfunction "1_1") (pintype "passive"))
    )
    (net (code "46") (name "Net-(DD4-PH0_{slash}OSC_IN{slash}FT)") (class "Default")
      (node (ref "DD4") (pin "5") (pinfunction "PH0_/OSC_IN/FT_5") (pintype "passive"))
      (node (ref "G1") (pin "3") (pinfunction "DCLK_3") (pintype "power_in"))
    )
    (net (code "47") (name "Net-(DD4-VCAP_1)") (class "Default")
      (node (ref "C54") (pin "2") (pinfunction "2_2") (pintype "passive"))
      (node (ref "DD4") (pin "31") (pinfunction "VCAP_1_31") (pintype "passive"))
    )
    (net (code "48") (name "Net-(DD4-VCAP_2)") (class "Default")
      (node (ref "C53") (pin "2") (pinfunction "2_2") (pintype "passive"))
      (node (ref "DD4") (pin "47") (pinfunction "VCAP_2_47") (pintype "passive"))
    )
    (net (code "49") (name "Net-(DD4-VDDA)") (class "Default")
      (node (ref "C56") (pin "2") (pinfunction "2_2") (pintype "passive"))
      (node (ref "C57") (pin "1") (pinfunction "1_1") (pintype "passive"))
      (node (ref "DD4") (pin "13") (pinfunction "VDDA_13") (pintype "passive"))
      (node (ref "L3") (pin "1") (pinfunction "1_1") (pintype "passive"))
    )
    (net (code "50") (name "Net-(R53-Pad1)") (class "Default")
      (node (ref "R53") (pin "1") (pinfunction "1_1") (pintype "passive"))
      (node (ref "X4") (pin "3") (pinfunction "3_3") (pintype "passive"))
    )
    (net (code "51") (name "Net-(R54-Pad1)") (class "Default")
      (node (ref "R54") (pin "1") (pinfunction "1_1") (pintype "passive"))
      (node (ref "X4") (pin "4") (pinfunction "4_4") (pintype "passive"))
    )
    (net (code "52") (name "Net-(R55-Pad1)") (class "Default")
      (node (ref "R55") (pin "1") (pinfunction "1_1") (pintype "passive"))
      (node (ref "X4") (pin "5") (pinfunction "5_5") (pintype "passive"))
    )
    (net (code "53") (name "Net-(R56-Pad1)") (class "Default")
      (node (ref "R56") (pin "1") (pinfunction "1_1") (pintype "passive"))
      (node (ref "X4") (pin "6") (pinfunction "6_6") (pintype "passive"))
    )
    (net (code "54") (name "Net-(R57-Pad1)") (class "Default")
      (node (ref "R57") (pin "1") (pinfunction "1_1") (pintype "passive"))
      (node (ref "X4") (pin "7") (pinfunction "7_7") (pintype "passive"))
    )
    (net (code "55") (name "Net-(R58-Pad1)") (class "Default")
      (node (ref "R58") (pin "1") (pinfunction "1_1") (pintype "passive"))
      (node (ref "X4") (pin "8") (pinfunction "8_8") (pintype "passive"))
    )
    (net (code "56") (name "Net-(VD5-K)") (class "Default")
      (node (ref "VD5") (pin "1") (pinfunction "K_1") (pintype "passive"))
      (node (ref "X4") (pin "1") (pinfunction "1_1") (pintype "passive"))
      (node (ref "X4") (pin "2") (pinfunction "2_2") (pintype "passive"))
    )
    (net (code "57") (name "unconnected-(DD4-A15_{slash}_JTDI{slash}SPI3_NSS{slash}I2S3_WS{slash}TIM2_CH1_ETR{slash}_SPI1_NSS{slash}FT-Pad50)") (class "Default")
      (node (ref "DD4") (pin "50") (pinfunction "A15_/_JTDI/SPI3_NSS/I2S3_WS/TIM2_CH1_ETR/_SPI1_NSS/FT_50") (pintype "passive"))
    )
    (net (code "58") (name "unconnected-(DD4-PA2_{slash}_USART2_TX{slash}TIM5_CH3{slash}ADC123_IN2{slash}TIM9_CH1{slash}TIM2_CH3{slash}ADC123_IN2{slash}FT-Pad16)") (class "Default")
      (node (ref "DD4") (pin "16") (pinfunction "PA2_/_USART2_TX/TIM5_CH3/ADC123_IN2/TIM9_CH1/TIM2_CH3/ADC123_IN2/FT_16") (pintype "passive"))
    )
    (net (code "59") (name "unconnected-(DD4-PA3_{slash}_USART2_RX{slash}TIM5_CH4{slash}TIM9_CH2{slash}TIM2_CH4{slash}OTG_HS_ULPI_D0{slash}ETH_MII_COL{slash}ADC123_IN3{slash}FT-Pad17)") (class "Default")
      (node (ref "DD4") (pin "17") (pinfunction "PA3_/_USART2_RX/TIM5_CH4/TIM9_CH2/TIM2_CH4/OTG_HS_ULPI_D0/ETH_MII_COL/ADC123_IN3/FT_17") (pintype "passive"))
    )
    (net (code "60") (name "unconnected-(DD4-PA4_{slash}_SPI1_NSS{slash}SPI3_NSS{slash}USART2_CK{slash}DCMI_HSYNC{slash}OTG_HS_SOF{slash}I2S3_WS{slash}ADC12_IN4{slash}DAC_OUT1{slash}TTa-Pad20)") (class "Default")
      (node (ref "DD4") (pin "20") (pinfunction "PA4_/_SPI1_NSS/SPI3_NSS/USART2_CK/DCMI_HSYNC/OTG_HS_SOF/I2S3_WS/ADC12_IN4/DAC_OUT1/TTa_20") (pintype "passive"))
    )
    (net (code "61") (name "unconnected-(DD4-PA5_{slash}_SPI1_SCK{slash}OTG_HS_ULPI_CK{slash}TIM2_CH1_ETR{slash}TIM8_CH1N{slash}ADC12_IN5{slash}DAC_OUT2{slash}TTa-Pad21)") (class "Default")
      (node (ref "DD4") (pin "21") (pinfunction "PA5_/_SPI1_SCK/OTG_HS_ULPI_CK/TIM2_CH1_ETR/TIM8_CH1N/ADC12_IN5/DAC_OUT2/TTa_21") (pintype "passive"))
    )
    (net (code "62") (name "unconnected-(DD4-PA6_{slash}_SPI1_MISO{slash}TIM8_BKIN{slash}TIM13_CH1{slash}DCMI_PIXCLK{slash}TIM3_CH1{slash}TIM1_BKIN{slash}ADC12_IN6{slash}FT-Pad22)") (class "Default")
      (node (ref "DD4") (pin "22") (pinfunction "PA6_/_SPI1_MISO/TIM8_BKIN/TIM13_CH1/DCMI_PIXCLK/TIM3_CH1/TIM1_BKIN/ADC12_IN6/FT_22") (pintype "passive"))
    )
    (net (code "63") (name "unconnected-(DD4-PA7_{slash}_SPI1_MOSI{slash}TIM8_CH1N{slash}TIM14_CH1{slash}TIM3_CH2{slash}ETH_MII_RX_DV{slash}TIM1_CH1N{slash}ETH_RMII_CRS_DV{slash}ADC12_IN7{slash}FT-Pad23)") (class "Default")
      (node (ref "DD4") (pin "23") (pinfunction "PA7_/_SPI1_MOSI/TIM8_CH1N/TIM14_CH1/TIM3_CH2/ETH_MII_RX_DV/TIM1_CH1N/ETH_RMII_CRS_DV/ADC12_IN7/FT_23") (pintype "passive"))
    )
    (net (code "64") (name "unconnected-(DD4-PB0_{slash}_TIM3_CH3{slash}TIM8_CH2N{slash}OTG_HS_ULPI_D1{slash}ETH_MII_RXD2{slash}TIM1_CH2N{slash}ADC12_IN8{slash}FT-Pad26)") (class "Default")
      (node (ref "DD4") (pin "26") (pinfunction "PB0_/_TIM3_CH3/TIM8_CH2N/OTG_HS_ULPI_D1/ETH_MII_RXD2/TIM1_CH2N/ADC12_IN8/FT_26") (pintype "passive"))
    )
    (net (code "65") (name "unconnected-(DD4-PB2_{slash}_BOOT1{slash}FT-Pad28)") (class "Default")
      (node (ref "DD4") (pin "28") (pinfunction "PB2_/_BOOT1/FT_28") (pintype "passive"))
    )
    (net (code "66") (name "unconnected-(DD4-PB4_{slash}_NJTRST{slash}SPI3_MISO{slash}TIM3_CH1{slash}SPI1_MISO{slash}I2S3ext_SD{slash}FT-Pad56)") (class "Default")
      (node (ref "DD4") (pin "56") (pinfunction "PB4_/_NJTRST/SPI3_MISO/TIM3_CH1/SPI1_MISO/I2S3ext_SD/FT_56") (pintype "passive"))
    )
    (net (code "67") (name "unconnected-(DD4-PB5_{slash}_I2C1_SMBA{slash}CAN2_RX{slash}OTG_HS_ULPI_D7{slash}ETH_PPS_OUT{slash}TIM3_CH2{slash}SPI1_MOSI{slash}SPI3_MOSI{slash}DCMI_D10{slash}I2S3_SD{slash}FT-Pad57)") (class "Default")
      (node (ref "DD4") (pin "57") (pinfunction "PB5_/_I2C1_SMBA/CAN2_RX/OTG_HS_ULPI_D7/ETH_PPS_OUT/TIM3_CH2/SPI1_MOSI/SPI3_MOSI/DCMI_D10/I2S3_SD/FT_57") (pintype "passive"))
    )
    (net (code "68") (name "unconnected-(DD4-PB8_{slash}_TIM4_CH3{slash}SDIO_D4{slash}TIM10_CH1{slash}DCMI_D6{slash}ETH_MII_TXD3{slash}I2C1_SCL{slash}CAN1_RX{slash}FT-Pad61)") (class "Default")
      (node (ref "DD4") (pin "61") (pinfunction "PB8_/_TIM4_CH3/SDIO_D4/TIM10_CH1/DCMI_D6/ETH_MII_TXD3/I2C1_SCL/CAN1_RX/FT_61") (pintype "passive"))
    )
    (net (code "69") (name "unconnected-(DD4-PB9_{slash}_SPI2_NSS{slash}I2S2_WS{slash}TIM4_CH4{slash}TIM11_CH1{slash}SDIO_D5{slash}DCMI_D7{slash}I2C1_SDA{slash}CAN1_TX{slash}FT-Pad62)") (class "Default")
      (node (ref "DD4") (pin "62") (pinfunction "PB9_/_SPI2_NSS/I2S2_WS/TIM4_CH4/TIM11_CH1/SDIO_D5/DCMI_D7/I2C1_SDA/CAN1_TX/FT_62") (pintype "passive"))
    )
    (net (code "70") (name "unconnected-(DD4-PC2_{slash}_SPI2_MISO{slash}OTG_HS_ULPI_DIR{slash}ETH_MII_TXD2{slash}I2S2ext_SD{slash}ADC123_IN12{slash}FT-Pad10)") (class "Default")
      (node (ref "DD4") (pin "10") (pinfunction "PC2_/_SPI2_MISO/OTG_HS_ULPI_DIR/ETH_MII_TXD2/I2S2ext_SD/ADC123_IN12/FT_10") (pintype "passive"))
    )
    (net (code "71") (name "unconnected-(DD4-PC3_{slash}_SPI2_MOSI{slash}I2S2_SD{slash}OTG_HS_ULPI_NXT{slash}ETH_MII_TX_CLK{slash}ADC123_IN13{slash}FT-Pad11)") (class "Default")
      (node (ref "DD4") (pin "11") (pinfunction "PC3_/_SPI2_MOSI/I2S2_SD/OTG_HS_ULPI_NXT/ETH_MII_TX_CLK/ADC123_IN13/FT_11") (pintype "passive"))
    )
    (net (code "72") (name "unconnected-(DD4-PC4_{slash}_ETH_RMII_RX_D0{slash}ETH_MII_RX_D0{slash}ADC12_IN14{slash}FT-Pad24)") (class "Default")
      (node (ref "DD4") (pin "24") (pinfunction "PC4_/_ETH_RMII_RX_D0/ETH_MII_RX_D0/ADC12_IN14/FT_24") (pintype "passive"))
    )
    (net (code "73") (name "unconnected-(DD4-PC5_{slash}_ETH_RMII_RX_D1{slash}ETH_MII_RX_D1{slash}ADC12_IN15{slash}FT-Pad25)") (class "Default")
      (node (ref "DD4") (pin "25") (pinfunction "PC5_/_ETH_RMII_RX_D1/ETH_MII_RX_D1/ADC12_IN15/FT_25") (pintype "passive"))
    )
    (net (code "74") (name "unconnected-(DD4-PC6_{slash}_I2S2_MCK{slash}TIM8_CH1{slash}SDIO_D6{slash}USART6_TX{slash}DCMI_D0{slash}TIM3_CH1{slash}FT-Pad37)") (class "Default")
      (node (ref "DD4") (pin "37") (pinfunction "PC6_/_I2S2_MCK/TIM8_CH1/SDIO_D6/USART6_TX/DCMI_D0/TIM3_CH1/FT_37") (pintype "passive"))
    )
    (net (code "75") (name "unconnected-(DD4-PC9_{slash}_I2S_CKIN{slash}MCO2{slash}TIM8_CH4{slash}SDIO_D1{slash}I2C3_SDA{slash}DCMI_D3{slash}TIM3_CH4{slash}FT-Pad40)") (class "Default")
      (node (ref "DD4") (pin "40") (pinfunction "PC9_/_I2S_CKIN/MCO2/TIM8_CH4/SDIO_D1/I2C3_SDA/DCMI_D3/TIM3_CH4/FT_40") (pintype "passive"))
    )
    (net (code "76") (name "unconnected-(DD4-PC10_{slash}_SPI3_SCK{slash}I2S3_CK{slash}UART4_TX{slash}SDIO_D2{slash}DCMI_D8{slash}USART3_TX{slash}FT-Pad51)") (class "Default")
      (node (ref "DD4") (pin "51") (pinfunction "PC10_/_SPI3_SCK/I2S3_CK/UART4_TX/SDIO_D2/DCMI_D8/USART3_TX/FT_51") (pintype "passive"))
    )
    (net (code "77") (name "unconnected-(DD4-PC11_{slash}_UART4_RX{slash}SPI3_MISO{slash}SDIO_D3{slash}DCMI_D4{slash}USART3_RX{slash}I2S3ext_SD{slash}FT-Pad52)") (class "Default")
      (node (ref "DD4") (pin "52") (pinfunction "PC11_/_UART4_RX/SPI3_MISO/SDIO_D3/DCMI_D4/USART3_RX/I2S3ext_SD/FT_52") (pintype "passive"))
    )
    (net (code "78") (name "unconnected-(DD4-PC12_{slash}_UART5_TX{slash}SDIO_CK{slash}DCMI_D9{slash}SPI3_MOSI{slash}I2S3_SD{slash}USART3_CK{slash}FT-Pad53)") (class "Default")
      (node (ref "DD4") (pin "53") (pinfunction "PC12_/_UART5_TX/SDIO_CK/DCMI_D9/SPI3_MOSI/I2S3_SD/USART3_CK/FT_53") (pintype "passive"))
    )
    (net (code "79") (name "unconnected-(DD4-PC13_{slash}_EVENTOUT{slash}RTC_OUT{slash}RTC_TAMP1{slash}RTC_TS{slash}FT-Pad2)") (class "Default")
      (node (ref "DD4") (pin "2") (pinfunction "PC13_/_EVENTOUT/RTC_OUT/RTC_TAMP1/RTC_TS/FT_2") (pintype "passive"))
    )
    (net (code "80") (name "unconnected-(DD4-PC14_{slash}_OSC32_IN{slash}FT-Pad3)") (class "Default")
      (node (ref "DD4") (pin "3") (pinfunction "PC14_/_OSC32_IN/FT_3") (pintype "passive"))
    )
    (net (code "81") (name "unconnected-(DD4-PC15_{slash}_OSC32_OUT{slash}FT-Pad4)") (class "Default")
      (node (ref "DD4") (pin "4") (pinfunction "PC15_/_OSC32_OUT/FT_4") (pintype "passive"))
    )
    (net (code "82") (name "unconnected-(DD4-PD2_{slash}_TIM3_ETR{slash}UART5_RX{slash}SDIO_CMD{slash}DCMI_D11{slash}FT-Pad54)") (class "Default")
      (node (ref "DD4") (pin "54") (pinfunction "PD2_/_TIM3_ETR/UART5_RX/SDIO_CMD/DCMI_D11/FT_54") (pintype "passive"))
    )
    (net (code "83") (name "unconnected-(DD4-PH1_{slash}OSC_OUT{slash}FT-Pad6)") (class "Default")
      (node (ref "DD4") (pin "6") (pinfunction "PH1_/OSC_OUT/FT_6") (pintype "passive+no_connect"))
    )
    (net (code "84") (name "unconnected-(DD6-NC-Pad4)") (class "Default")
      (node (ref "DD6") (pin "4") (pinfunction "NC_4") (pintype "passive+no_connect"))
    )
    (net (code "85") (name "unconnected-(DD6-NC-Pad5)") (class "Default")
      (node (ref "DD6") (pin "5") (pinfunction "NC_5") (pintype "passive+no_connect"))
    )
    (net (code "86") (name "unconnected-(DD6-NC-Pad11)") (class "Default")
      (node (ref "DD6") (pin "11") (pinfunction "NC_11") (pintype "passive+no_connect"))
    )
    (net (code "87") (name "unconnected-(DD6-NC-Pad14)") (class "Default")
      (node (ref "DD6") (pin "14") (pinfunction "NC_14") (pintype "passive+no_connect"))
    )
    (net (code "88") (name "unconnected-(G1-NC-Pad1)") (class "Default")
      (node (ref "G1") (pin "1") (pinfunction "NC_1") (pintype "power_in+no_connect"))
    )
  )
)
